# 08-DPLL-2.net
KiCad netlist of a schematic drawn in Altium Designer
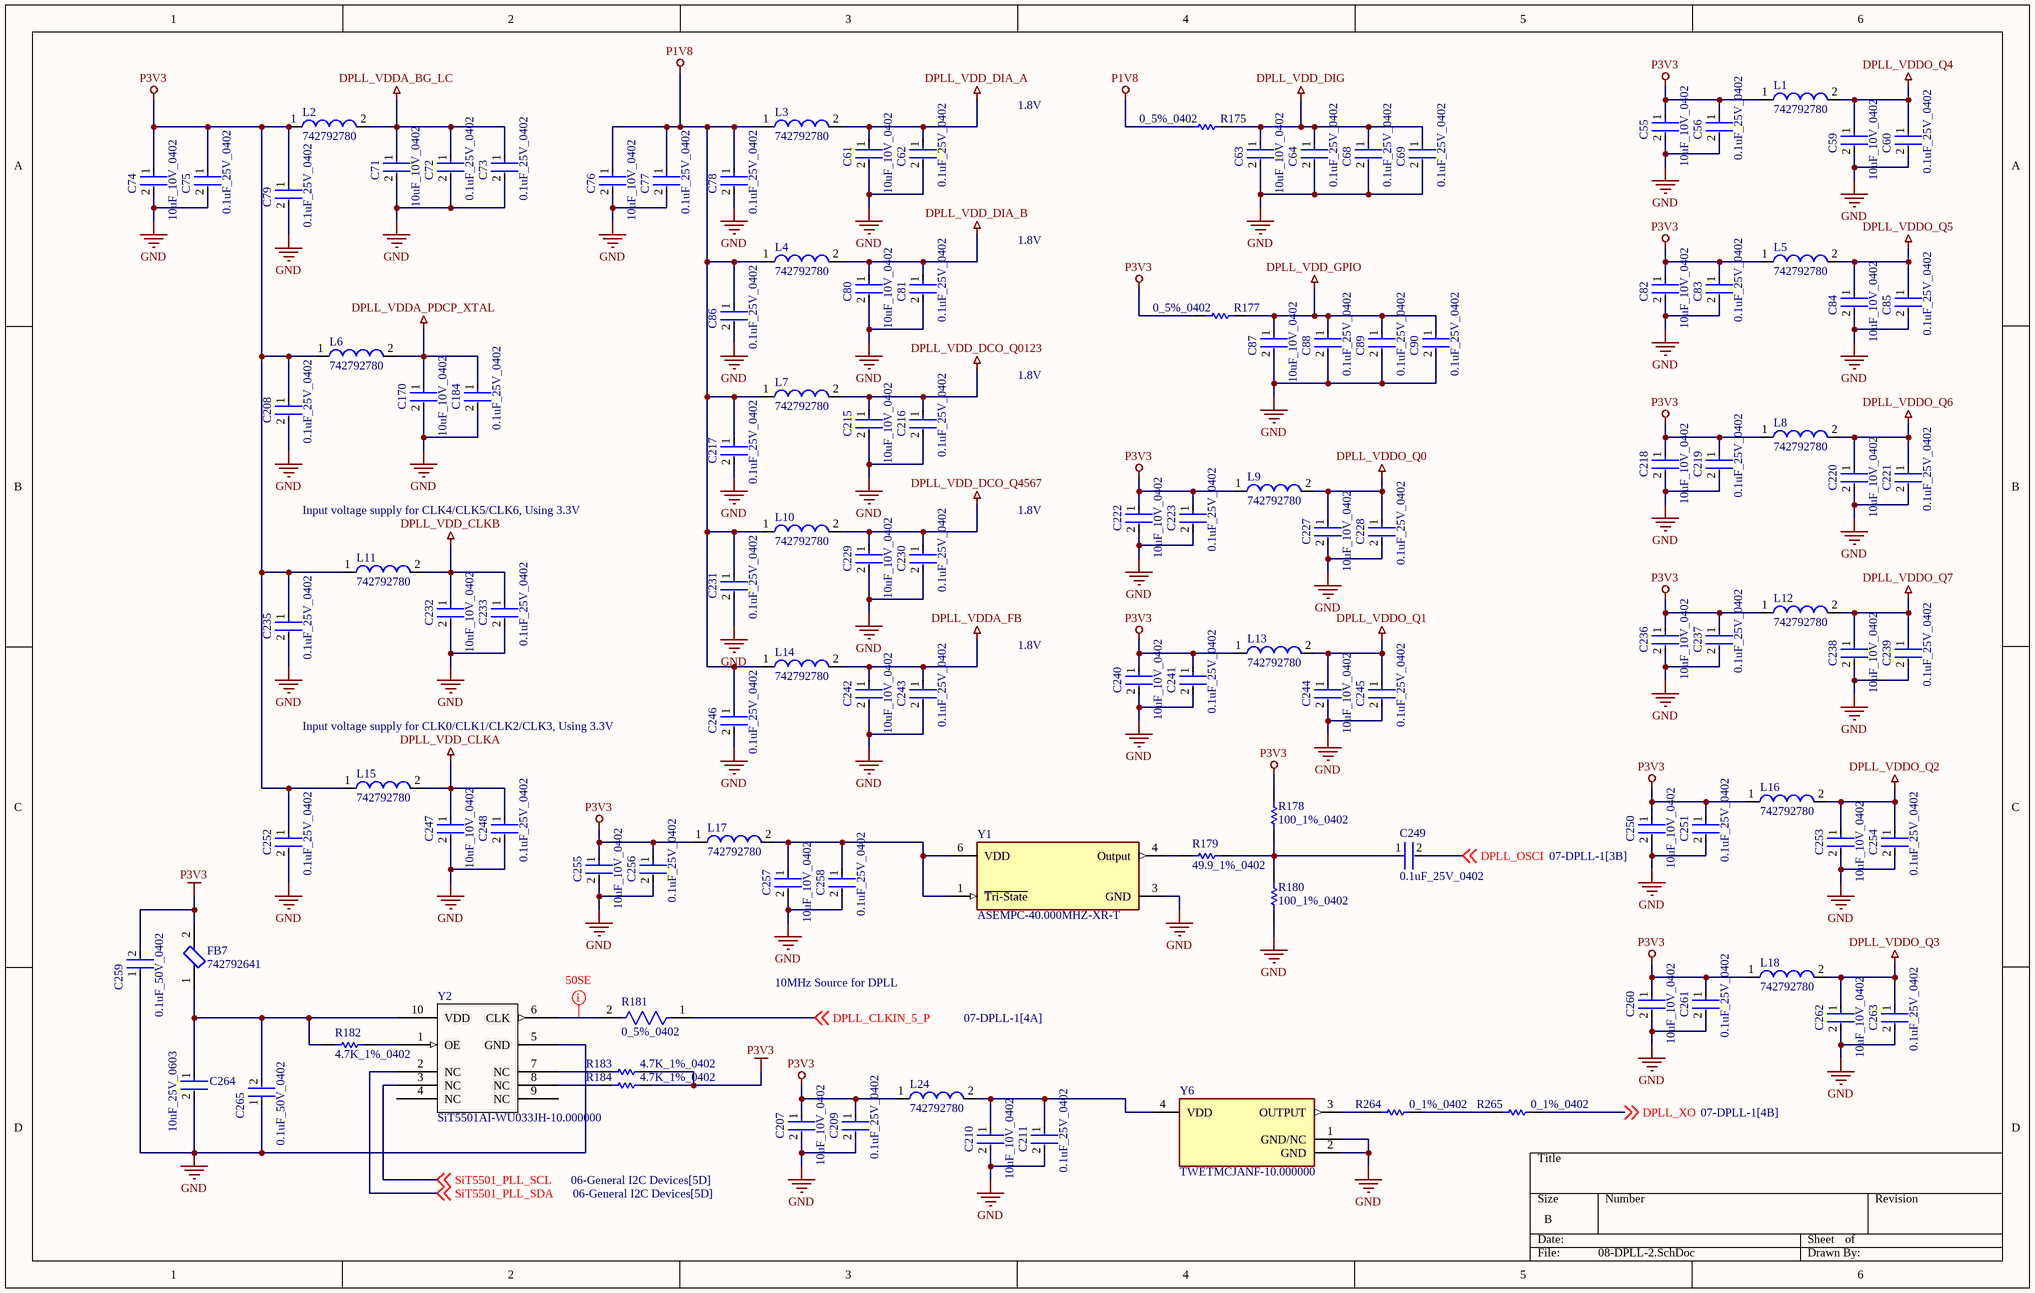
[diagram p0: 08-DPLL-2.SchDoc]

(export (version "E")
  (design (tool "Eeschema 10.0.6"))
  (components
    (comp (ref "C55")
      (value "10uF_10V_0402")
      (footprint "FP-CL05A106MP5NUNC-MFG")
      (description "CAP CER 10UF 10V X5R 0402")
      (fields
        (field (name "OCTOPART") "https://octopart.com/cl05a106mp5nunc-samsung-22457395")
        (field (name "TOLERANCE") "20%")
      )
      (libsource (lib "Altium Content Vault") (part "b4654b650e69147ec39a6b967a45e02"))
    )
    (comp (ref "C56")
      (value "0.1uF_25V_0402")
      (footprint "FP-0402-L_1_0_1-W_0_5_0_1-IPC_C")
      (description "General Purpose Ceramic Capacitor, 0402, 100nF, 10%, X7R, 15%, 25V")
      (fields (field (name "VOLTAGE") "25V") (field (name "TOLERANCE") "10%"))
      (libsource (lib "Altium Content Vault") (part "b4654b650e69147ec39a6b967a45e02"))
    )
    (comp (ref "C59")
      (value "10uF_10V_0402")
      (footprint "FP-CL05A106MP5NUNC-MFG")
      (description "CAP CER 10UF 10V X5R 0402")
      (fields
        (field (name "OCTOPART") "https://octopart.com/cl05a106mp5nunc-samsung-22457395")
        (field (name "TOLERANCE") "20%")
      )
      (libsource (lib "Altium Content Vault") (part "b4654b650e69147ec39a6b967a45e02"))
    )
    (comp (ref "C60")
      (value "0.1uF_25V_0402")
      (footprint "FP-0402-L_1_0_1-W_0_5_0_1-IPC_C")
      (description "General Purpose Ceramic Capacitor, 0402, 100nF, 10%, X7R, 15%, 25V")
      (fields (field (name "VOLTAGE") "25V") (field (name "TOLERANCE") "10%"))
      (libsource (lib "Altium Content Vault") (part "b4654b650e69147ec39a6b967a45e02"))
    )
    (comp (ref "C61")
      (value "10uF_10V_0402")
      (footprint "FP-CL05A106MP5NUNC-MFG")
      (description "CAP CER 10UF 10V X5R 0402")
      (fields
        (field (name "OCTOPART") "https://octopart.com/cl05a106mp5nunc-samsung-22457395")
        (field (name "TOLERANCE") "20%")
      )
      (libsource (lib "Altium Content Vault") (part "b4654b650e69147ec39a6b967a45e02"))
    )
    (comp (ref "C62")
      (value "0.1uF_25V_0402")
      (footprint "FP-0402-L_1_0_1-W_0_5_0_1-IPC_C")
      (description "General Purpose Ceramic Capacitor, 0402, 100nF, 10%, X7R, 15%, 25V")
      (fields (field (name "VOLTAGE") "25V") (field (name "TOLERANCE") "10%"))
      (libsource (lib "Altium Content Vault") (part "b4654b650e69147ec39a6b967a45e02"))
    )
    (comp (ref "C63")
      (value "10uF_10V_0402")
      (footprint "FP-CL05A106MP5NUNC-MFG")
      (description "CAP CER 10UF 10V X5R 0402")
      (fields
        (field (name "OCTOPART") "https://octopart.com/cl05a106mp5nunc-samsung-22457395")
        (field (name "TOLERANCE") "20%")
      )
      (libsource (lib "Altium Content Vault") (part "b4654b650e69147ec39a6b967a45e02"))
    )
    (comp (ref "C64")
      (value "0.1uF_25V_0402")
      (footprint "FP-0402-L_1_0_1-W_0_5_0_1-IPC_C")
      (description "General Purpose Ceramic Capacitor, 0402, 100nF, 10%, X7R, 15%, 25V")
      (fields (field (name "VOLTAGE") "25V") (field (name "TOLERANCE") "10%"))
      (libsource (lib "Altium Content Vault") (part "b4654b650e69147ec39a6b967a45e02"))
    )
    (comp (ref "C68")
      (value "0.1uF_25V_0402")
      (footprint "FP-0402-L_1_0_1-W_0_5_0_1-IPC_C")
      (description "General Purpose Ceramic Capacitor, 0402, 100nF, 10%, X7R, 15%, 25V")
      (fields (field (name "VOLTAGE") "25V") (field (name "TOLERANCE") "10%"))
      (libsource (lib "Altium Content Vault") (part "b4654b650e69147ec39a6b967a45e02"))
    )
    (comp (ref "C69")
      (value "0.1uF_25V_0402")
      (footprint "FP-0402-L_1_0_1-W_0_5_0_1-IPC_C")
      (description "General Purpose Ceramic Capacitor, 0402, 100nF, 10%, X7R, 15%, 25V")
      (fields (field (name "VOLTAGE") "25V") (field (name "TOLERANCE") "10%"))
      (libsource (lib "Altium Content Vault") (part "b4654b650e69147ec39a6b967a45e02"))
    )
    (comp (ref "C71")
      (value "10uF_10V_0402")
      (footprint "FP-CL05A106MP5NUNC-MFG")
      (description "CAP CER 10UF 10V X5R 0402")
      (fields
        (field (name "OCTOPART") "https://octopart.com/cl05a106mp5nunc-samsung-22457395")
        (field (name "TOLERANCE") "20%")
      )
      (libsource (lib "Altium Content Vault") (part "b4654b650e69147ec39a6b967a45e02"))
    )
    (comp (ref "C72")
      (value "0.1uF_25V_0402")
      (footprint "FP-0402-L_1_0_1-W_0_5_0_1-IPC_C")
      (description "General Purpose Ceramic Capacitor, 0402, 100nF, 10%, X7R, 15%, 25V")
      (fields (field (name "VOLTAGE") "25V") (field (name "TOLERANCE") "10%"))
      (libsource (lib "Altium Content Vault") (part "b4654b650e69147ec39a6b967a45e02"))
    )
    (comp (ref "C73")
      (value "0.1uF_25V_0402")
      (footprint "FP-0402-L_1_0_1-W_0_5_0_1-IPC_C")
      (description "General Purpose Ceramic Capacitor, 0402, 100nF, 10%, X7R, 15%, 25V")
      (fields (field (name "VOLTAGE") "25V") (field (name "TOLERANCE") "10%"))
      (libsource (lib "Altium Content Vault") (part "b4654b650e69147ec39a6b967a45e02"))
    )
    (comp (ref "C74")
      (value "10uF_10V_0402")
      (footprint "FP-CL05A106MP5NUNC-MFG")
      (description "CAP CER 10UF 10V X5R 0402")
      (fields
        (field (name "OCTOPART") "https://octopart.com/cl05a106mp5nunc-samsung-22457395")
        (field (name "TOLERANCE") "20%")
      )
      (libsource (lib "Altium Content Vault") (part "b4654b650e69147ec39a6b967a45e02"))
    )
    (comp (ref "C75")
      (value "0.1uF_25V_0402")
      (footprint "FP-0402-L_1_0_1-W_0_5_0_1-IPC_C")
      (description "General Purpose Ceramic Capacitor, 0402, 100nF, 10%, X7R, 15%, 25V")
      (fields (field (name "VOLTAGE") "25V") (field (name "TOLERANCE") "10%"))
      (libsource (lib "Altium Content Vault") (part "b4654b650e69147ec39a6b967a45e02"))
    )
    (comp (ref "C76")
      (value "10uF_10V_0402")
      (footprint "FP-CL05A106MP5NUNC-MFG")
      (description "CAP CER 10UF 10V X5R 0402")
      (fields
        (field (name "OCTOPART") "https://octopart.com/cl05a106mp5nunc-samsung-22457395")
        (field (name "TOLERANCE") "20%")
      )
      (libsource (lib "Altium Content Vault") (part "b4654b650e69147ec39a6b967a45e02"))
    )
    (comp (ref "C77")
      (value "0.1uF_25V_0402")
      (footprint "FP-0402-L_1_0_1-W_0_5_0_1-IPC_C")
      (description "General Purpose Ceramic Capacitor, 0402, 100nF, 10%, X7R, 15%, 25V")
      (fields (field (name "VOLTAGE") "25V") (field (name "TOLERANCE") "10%"))
      (libsource (lib "Altium Content Vault") (part "b4654b650e69147ec39a6b967a45e02"))
    )
    (comp (ref "C78")
      (value "0.1uF_25V_0402")
      (footprint "FP-0402-L_1_0_1-W_0_5_0_1-IPC_C")
      (description "General Purpose Ceramic Capacitor, 0402, 100nF, 10%, X7R, 15%, 25V")
      (fields (field (name "VOLTAGE") "25V") (field (name "TOLERANCE") "10%"))
      (libsource (lib "Altium Content Vault") (part "b4654b650e69147ec39a6b967a45e02"))
    )
    (comp (ref "C79")
      (value "0.1uF_25V_0402")
      (footprint "FP-0402-L_1_0_1-W_0_5_0_1-IPC_C")
      (description "General Purpose Ceramic Capacitor, 0402, 100nF, 10%, X7R, 15%, 25V")
      (fields (field (name "VOLTAGE") "25V") (field (name "TOLERANCE") "10%"))
      (libsource (lib "Altium Content Vault") (part "b4654b650e69147ec39a6b967a45e02"))
    )
    (comp (ref "C80")
      (value "10uF_10V_0402")
      (footprint "FP-CL05A106MP5NUNC-MFG")
      (description "CAP CER 10UF 10V X5R 0402")
      (fields
        (field (name "OCTOPART") "https://octopart.com/cl05a106mp5nunc-samsung-22457395")
        (field (name "TOLERANCE") "20%")
      )
      (libsource (lib "Altium Content Vault") (part "b4654b650e69147ec39a6b967a45e02"))
    )
    (comp (ref "C81")
      (value "0.1uF_25V_0402")
      (footprint "FP-0402-L_1_0_1-W_0_5_0_1-IPC_C")
      (description "General Purpose Ceramic Capacitor, 0402, 100nF, 10%, X7R, 15%, 25V")
      (fields (field (name "VOLTAGE") "25V") (field (name "TOLERANCE") "10%"))
      (libsource (lib "Altium Content Vault") (part "b4654b650e69147ec39a6b967a45e02"))
    )
    (comp (ref "C82")
      (value "10uF_10V_0402")
      (footprint "FP-CL05A106MP5NUNC-MFG")
      (description "CAP CER 10UF 10V X5R 0402")
      (fields
        (field (name "OCTOPART") "https://octopart.com/cl05a106mp5nunc-samsung-22457395")
        (field (name "TOLERANCE") "20%")
      )
      (libsource (lib "Altium Content Vault") (part "b4654b650e69147ec39a6b967a45e02"))
    )
    (comp (ref "C83")
      (value "0.1uF_25V_0402")
      (footprint "FP-0402-L_1_0_1-W_0_5_0_1-IPC_C")
      (description "General Purpose Ceramic Capacitor, 0402, 100nF, 10%, X7R, 15%, 25V")
      (fields (field (name "VOLTAGE") "25V") (field (name "TOLERANCE") "10%"))
      (libsource (lib "Altium Content Vault") (part "b4654b650e69147ec39a6b967a45e02"))
    )
    (comp (ref "C84")
      (value "10uF_10V_0402")
      (footprint "FP-CL05A106MP5NUNC-MFG")
      (description "CAP CER 10UF 10V X5R 0402")
      (fields
        (field (name "OCTOPART") "https://octopart.com/cl05a106mp5nunc-samsung-22457395")
        (field (name "TOLERANCE") "20%")
      )
      (libsource (lib "Altium Content Vault") (part "b4654b650e69147ec39a6b967a45e02"))
    )
    (comp (ref "C85")
      (value "0.1uF_25V_0402")
      (footprint "FP-0402-L_1_0_1-W_0_5_0_1-IPC_C")
      (description "General Purpose Ceramic Capacitor, 0402, 100nF, 10%, X7R, 15%, 25V")
      (fields (field (name "VOLTAGE") "25V") (field (name "TOLERANCE") "10%"))
      (libsource (lib "Altium Content Vault") (part "b4654b650e69147ec39a6b967a45e02"))
    )
    (comp (ref "C86")
      (value "0.1uF_25V_0402")
      (footprint "FP-0402-L_1_0_1-W_0_5_0_1-IPC_C")
      (description "General Purpose Ceramic Capacitor, 0402, 100nF, 10%, X7R, 15%, 25V")
      (fields (field (name "VOLTAGE") "25V") (field (name "TOLERANCE") "10%"))
      (libsource (lib "Altium Content Vault") (part "b4654b650e69147ec39a6b967a45e02"))
    )
    (comp (ref "C87")
      (value "10uF_10V_0402")
      (footprint "FP-CL05A106MP5NUNC-MFG")
      (description "CAP CER 10UF 10V X5R 0402")
      (fields
        (field (name "OCTOPART") "https://octopart.com/cl05a106mp5nunc-samsung-22457395")
        (field (name "TOLERANCE") "20%")
      )
      (libsource (lib "Altium Content Vault") (part "b4654b650e69147ec39a6b967a45e02"))
    )
    (comp (ref "C88")
      (value "0.1uF_25V_0402")
      (footprint "FP-0402-L_1_0_1-W_0_5_0_1-IPC_C")
      (description "General Purpose Ceramic Capacitor, 0402, 100nF, 10%, X7R, 15%, 25V")
      (fields (field (name "VOLTAGE") "25V") (field (name "TOLERANCE") "10%"))
      (libsource (lib "Altium Content Vault") (part "b4654b650e69147ec39a6b967a45e02"))
    )
    (comp (ref "C89")
      (value "0.1uF_25V_0402")
      (footprint "FP-0402-L_1_0_1-W_0_5_0_1-IPC_C")
      (description "General Purpose Ceramic Capacitor, 0402, 100nF, 10%, X7R, 15%, 25V")
      (fields (field (name "VOLTAGE") "25V") (field (name "TOLERANCE") "10%"))
      (libsource (lib "Altium Content Vault") (part "b4654b650e69147ec39a6b967a45e02"))
    )
    (comp (ref "C90")
      (value "0.1uF_25V_0402")
      (footprint "FP-0402-L_1_0_1-W_0_5_0_1-IPC_C")
      (description "General Purpose Ceramic Capacitor, 0402, 100nF, 10%, X7R, 15%, 25V")
      (fields (field (name "VOLTAGE") "25V") (field (name "TOLERANCE") "10%"))
      (libsource (lib "Altium Content Vault") (part "b4654b650e69147ec39a6b967a45e02"))
    )
    (comp (ref "C170")
      (value "10uF_10V_0402")
      (footprint "FP-CL05A106MP5NUNC-MFG")
      (description "CAP CER 10UF 10V X5R 0402")
      (fields
        (field (name "OCTOPART") "https://octopart.com/cl05a106mp5nunc-samsung-22457395")
        (field (name "TOLERANCE") "20%")
      )
      (libsource (lib "Altium Content Vault") (part "b4654b650e69147ec39a6b967a45e02"))
    )
    (comp (ref "C184")
      (value "0.1uF_25V_0402")
      (footprint "FP-0402-L_1_0_1-W_0_5_0_1-IPC_C")
      (description "General Purpose Ceramic Capacitor, 0402, 100nF, 10%, X7R, 15%, 25V")
      (fields (field (name "VOLTAGE") "25V") (field (name "TOLERANCE") "10%"))
      (libsource (lib "Altium Content Vault") (part "b4654b650e69147ec39a6b967a45e02"))
    )
    (comp (ref "C207")
      (value "10uF_10V_0402")
      (footprint "FP-CL05A106MP5NUNC-MFG")
      (description "CAP CER 10UF 10V X5R 0402")
      (fields
        (field (name "OCTOPART") "https://octopart.com/cl05a106mp5nunc-samsung-22457395")
        (field (name "TOLERANCE") "20%")
      )
      (libsource (lib "Altium Content Vault") (part "b4654b650e69147ec39a6b967a45e02"))
    )
    (comp (ref "C208")
      (value "0.1uF_25V_0402")
      (footprint "FP-0402-L_1_0_1-W_0_5_0_1-IPC_C")
      (description "General Purpose Ceramic Capacitor, 0402, 100nF, 10%, X7R, 15%, 25V")
      (fields (field (name "VOLTAGE") "25V") (field (name "TOLERANCE") "10%"))
      (libsource (lib "Altium Content Vault") (part "b4654b650e69147ec39a6b967a45e02"))
    )
    (comp (ref "C209")
      (value "0.1uF_25V_0402")
      (footprint "FP-0402-L_1_0_1-W_0_5_0_1-IPC_C")
      (description "General Purpose Ceramic Capacitor, 0402, 100nF, 10%, X7R, 15%, 25V")
      (fields (field (name "VOLTAGE") "25V") (field (name "TOLERANCE") "10%"))
      (libsource (lib "Altium Content Vault") (part "b4654b650e69147ec39a6b967a45e02"))
    )
    (comp (ref "C210")
      (value "10uF_10V_0402")
      (footprint "FP-CL05A106MP5NUNC-MFG")
      (description "CAP CER 10UF 10V X5R 0402")
      (fields
        (field (name "OCTOPART") "https://octopart.com/cl05a106mp5nunc-samsung-22457395")
        (field (name "TOLERANCE") "20%")
      )
      (libsource (lib "Altium Content Vault") (part "b4654b650e69147ec39a6b967a45e02"))
    )
    (comp (ref "C211")
      (value "0.1uF_25V_0402")
      (footprint "FP-0402-L_1_0_1-W_0_5_0_1-IPC_C")
      (description "General Purpose Ceramic Capacitor, 0402, 100nF, 10%, X7R, 15%, 25V")
      (fields (field (name "VOLTAGE") "25V") (field (name "TOLERANCE") "10%"))
      (libsource (lib "Altium Content Vault") (part "b4654b650e69147ec39a6b967a45e02"))
    )
    (comp (ref "C215")
      (value "10uF_10V_0402")
      (footprint "FP-CL05A106MP5NUNC-MFG")
      (description "CAP CER 10UF 10V X5R 0402")
      (fields
        (field (name "OCTOPART") "https://octopart.com/cl05a106mp5nunc-samsung-22457395")
        (field (name "TOLERANCE") "20%")
      )
      (libsource (lib "Altium Content Vault") (part "b4654b650e69147ec39a6b967a45e02"))
    )
    (comp (ref "C216")
      (value "0.1uF_25V_0402")
      (footprint "FP-0402-L_1_0_1-W_0_5_0_1-IPC_C")
      (description "General Purpose Ceramic Capacitor, 0402, 100nF, 10%, X7R, 15%, 25V")
      (fields (field (name "VOLTAGE") "25V") (field (name "TOLERANCE") "10%"))
      (libsource (lib "Altium Content Vault") (part "b4654b650e69147ec39a6b967a45e02"))
    )
    (comp (ref "C217")
      (value "0.1uF_25V_0402")
      (footprint "FP-0402-L_1_0_1-W_0_5_0_1-IPC_C")
      (description "General Purpose Ceramic Capacitor, 0402, 100nF, 10%, X7R, 15%, 25V")
      (fields (field (name "VOLTAGE") "25V") (field (name "TOLERANCE") "10%"))
      (libsource (lib "Altium Content Vault") (part "b4654b650e69147ec39a6b967a45e02"))
    )
    (comp (ref "C218")
      (value "10uF_10V_0402")
      (footprint "FP-CL05A106MP5NUNC-MFG")
      (description "CAP CER 10UF 10V X5R 0402")
      (fields
        (field (name "OCTOPART") "https://octopart.com/cl05a106mp5nunc-samsung-22457395")
        (field (name "TOLERANCE") "20%")
      )
      (libsource (lib "Altium Content Vault") (part "b4654b650e69147ec39a6b967a45e02"))
    )
    (comp (ref "C219")
      (value "0.1uF_25V_0402")
      (footprint "FP-0402-L_1_0_1-W_0_5_0_1-IPC_C")
      (description "General Purpose Ceramic Capacitor, 0402, 100nF, 10%, X7R, 15%, 25V")
      (fields (field (name "VOLTAGE") "25V") (field (name "TOLERANCE") "10%"))
      (libsource (lib "Altium Content Vault") (part "b4654b650e69147ec39a6b967a45e02"))
    )
    (comp (ref "C220")
      (value "10uF_10V_0402")
      (footprint "FP-CL05A106MP5NUNC-MFG")
      (description "CAP CER 10UF 10V X5R 0402")
      (fields
        (field (name "OCTOPART") "https://octopart.com/cl05a106mp5nunc-samsung-22457395")
        (field (name "TOLERANCE") "20%")
      )
      (libsource (lib "Altium Content Vault") (part "b4654b650e69147ec39a6b967a45e02"))
    )
    (comp (ref "C221")
      (value "0.1uF_25V_0402")
      (footprint "FP-0402-L_1_0_1-W_0_5_0_1-IPC_C")
      (description "General Purpose Ceramic Capacitor, 0402, 100nF, 10%, X7R, 15%, 25V")
      (fields (field (name "VOLTAGE") "25V") (field (name "TOLERANCE") "10%"))
      (libsource (lib "Altium Content Vault") (part "b4654b650e69147ec39a6b967a45e02"))
    )
    (comp (ref "C222")
      (value "10uF_10V_0402")
      (footprint "FP-CL05A106MP5NUNC-MFG")
      (description "CAP CER 10UF 10V X5R 0402")
      (fields
        (field (name "OCTOPART") "https://octopart.com/cl05a106mp5nunc-samsung-22457395")
        (field (name "TOLERANCE") "20%")
      )
      (libsource (lib "Altium Content Vault") (part "b4654b650e69147ec39a6b967a45e02"))
    )
    (comp (ref "C223")
      (value "0.1uF_25V_0402")
      (footprint "FP-0402-L_1_0_1-W_0_5_0_1-IPC_C")
      (description "General Purpose Ceramic Capacitor, 0402, 100nF, 10%, X7R, 15%, 25V")
      (fields (field (name "VOLTAGE") "25V") (field (name "TOLERANCE") "10%"))
      (libsource (lib "Altium Content Vault") (part "b4654b650e69147ec39a6b967a45e02"))
    )
    (comp (ref "C227")
      (value "10uF_10V_0402")
      (footprint "FP-CL05A106MP5NUNC-MFG")
      (description "CAP CER 10UF 10V X5R 0402")
      (fields
        (field (name "OCTOPART") "https://octopart.com/cl05a106mp5nunc-samsung-22457395")
        (field (name "TOLERANCE") "20%")
      )
      (libsource (lib "Altium Content Vault") (part "b4654b650e69147ec39a6b967a45e02"))
    )
    (comp (ref "C228")
      (value "0.1uF_25V_0402")
      (footprint "FP-0402-L_1_0_1-W_0_5_0_1-IPC_C")
      (description "General Purpose Ceramic Capacitor, 0402, 100nF, 10%, X7R, 15%, 25V")
      (fields (field (name "VOLTAGE") "25V") (field (name "TOLERANCE") "10%"))
      (libsource (lib "Altium Content Vault") (part "b4654b650e69147ec39a6b967a45e02"))
    )
    (comp (ref "C229")
      (value "10uF_10V_0402")
      (footprint "FP-CL05A106MP5NUNC-MFG")
      (description "CAP CER 10UF 10V X5R 0402")
      (fields
        (field (name "OCTOPART") "https://octopart.com/cl05a106mp5nunc-samsung-22457395")
        (field (name "TOLERANCE") "20%")
      )
      (libsource (lib "Altium Content Vault") (part "b4654b650e69147ec39a6b967a45e02"))
    )
    (comp (ref "C230")
      (value "0.1uF_25V_0402")
      (footprint "FP-0402-L_1_0_1-W_0_5_0_1-IPC_C")
      (description "General Purpose Ceramic Capacitor, 0402, 100nF, 10%, X7R, 15%, 25V")
      (fields (field (name "VOLTAGE") "25V") (field (name "TOLERANCE") "10%"))
      (libsource (lib "Altium Content Vault") (part "b4654b650e69147ec39a6b967a45e02"))
    )
    (comp (ref "C231")
      (value "0.1uF_25V_0402")
      (footprint "FP-0402-L_1_0_1-W_0_5_0_1-IPC_C")
      (description "General Purpose Ceramic Capacitor, 0402, 100nF, 10%, X7R, 15%, 25V")
      (fields (field (name "VOLTAGE") "25V") (field (name "TOLERANCE") "10%"))
      (libsource (lib "Altium Content Vault") (part "b4654b650e69147ec39a6b967a45e02"))
    )
    (comp (ref "C232")
      (value "10uF_10V_0402")
      (footprint "FP-CL05A106MP5NUNC-MFG")
      (description "CAP CER 10UF 10V X5R 0402")
      (fields
        (field (name "OCTOPART") "https://octopart.com/cl05a106mp5nunc-samsung-22457395")
        (field (name "TOLERANCE") "20%")
      )
      (libsource (lib "Altium Content Vault") (part "b4654b650e69147ec39a6b967a45e02"))
    )
    (comp (ref "C233")
      (value "0.1uF_25V_0402")
      (footprint "FP-0402-L_1_0_1-W_0_5_0_1-IPC_C")
      (description "General Purpose Ceramic Capacitor, 0402, 100nF, 10%, X7R, 15%, 25V")
      (fields (field (name "VOLTAGE") "25V") (field (name "TOLERANCE") "10%"))
      (libsource (lib "Altium Content Vault") (part "b4654b650e69147ec39a6b967a45e02"))
    )
    (comp (ref "C235")
      (value "0.1uF_25V_0402")
      (footprint "FP-0402-L_1_0_1-W_0_5_0_1-IPC_C")
      (description "General Purpose Ceramic Capacitor, 0402, 100nF, 10%, X7R, 15%, 25V")
      (fields (field (name "VOLTAGE") "25V") (field (name "TOLERANCE") "10%"))
      (libsource (lib "Altium Content Vault") (part "b4654b650e69147ec39a6b967a45e02"))
    )
    (comp (ref "C236")
      (value "10uF_10V_0402")
      (footprint "FP-CL05A106MP5NUNC-MFG")
      (description "CAP CER 10UF 10V X5R 0402")
      (fields
        (field (name "OCTOPART") "https://octopart.com/cl05a106mp5nunc-samsung-22457395")
        (field (name "TOLERANCE") "20%")
      )
      (libsource (lib "Altium Content Vault") (part "b4654b650e69147ec39a6b967a45e02"))
    )
    (comp (ref "C237")
      (value "0.1uF_25V_0402")
      (footprint "FP-0402-L_1_0_1-W_0_5_0_1-IPC_C")
      (description "General Purpose Ceramic Capacitor, 0402, 100nF, 10%, X7R, 15%, 25V")
      (fields (field (name "VOLTAGE") "25V") (field (name "TOLERANCE") "10%"))
      (libsource (lib "Altium Content Vault") (part "b4654b650e69147ec39a6b967a45e02"))
    )
    (comp (ref "C238")
      (value "10uF_10V_0402")
      (footprint "FP-CL05A106MP5NUNC-MFG")
      (description "CAP CER 10UF 10V X5R 0402")
      (fields
        (field (name "OCTOPART") "https://octopart.com/cl05a106mp5nunc-samsung-22457395")
        (field (name "TOLERANCE") "20%")
      )
      (libsource (lib "Altium Content Vault") (part "b4654b650e69147ec39a6b967a45e02"))
    )
    (comp (ref "C239")
      (value "0.1uF_25V_0402")
      (footprint "FP-0402-L_1_0_1-W_0_5_0_1-IPC_C")
      (description "General Purpose Ceramic Capacitor, 0402, 100nF, 10%, X7R, 15%, 25V")
      (fields (field (name "VOLTAGE") "25V") (field (name "TOLERANCE") "10%"))
      (libsource (lib "Altium Content Vault") (part "b4654b650e69147ec39a6b967a45e02"))
    )
    (comp (ref "C240")
      (value "10uF_10V_0402")
      (footprint "FP-CL05A106MP5NUNC-MFG")
      (description "CAP CER 10UF 10V X5R 0402")
      (fields
        (field (name "OCTOPART") "https://octopart.com/cl05a106mp5nunc-samsung-22457395")
        (field (name "TOLERANCE") "20%")
      )
      (libsource (lib "Altium Content Vault") (part "b4654b650e69147ec39a6b967a45e02"))
    )
    (comp (ref "C241")
      (value "0.1uF_25V_0402")
      (footprint "FP-0402-L_1_0_1-W_0_5_0_1-IPC_C")
      (description "General Purpose Ceramic Capacitor, 0402, 100nF, 10%, X7R, 15%, 25V")
      (fields (field (name "VOLTAGE") "25V") (field (name "TOLERANCE") "10%"))
      (libsource (lib "Altium Content Vault") (part "b4654b650e69147ec39a6b967a45e02"))
    )
    (comp (ref "C242")
      (value "10uF_10V_0402")
      (footprint "FP-CL05A106MP5NUNC-MFG")
      (description "CAP CER 10UF 10V X5R 0402")
      (fields
        (field (name "OCTOPART") "https://octopart.com/cl05a106mp5nunc-samsung-22457395")
        (field (name "TOLERANCE") "20%")
      )
      (libsource (lib "Altium Content Vault") (part "b4654b650e69147ec39a6b967a45e02"))
    )
    (comp (ref "C243")
      (value "0.1uF_25V_0402")
      (footprint "FP-0402-L_1_0_1-W_0_5_0_1-IPC_C")
      (description "General Purpose Ceramic Capacitor, 0402, 100nF, 10%, X7R, 15%, 25V")
      (fields (field (name "VOLTAGE") "25V") (field (name "TOLERANCE") "10%"))
      (libsource (lib "Altium Content Vault") (part "b4654b650e69147ec39a6b967a45e02"))
    )
    (comp (ref "C244")
      (value "10uF_10V_0402")
      (footprint "FP-CL05A106MP5NUNC-MFG")
      (description "CAP CER 10UF 10V X5R 0402")
      (fields
        (field (name "OCTOPART") "https://octopart.com/cl05a106mp5nunc-samsung-22457395")
        (field (name "TOLERANCE") "20%")
      )
      (libsource (lib "Altium Content Vault") (part "b4654b650e69147ec39a6b967a45e02"))
    )
    (comp (ref "C245")
      (value "0.1uF_25V_0402")
      (footprint "FP-0402-L_1_0_1-W_0_5_0_1-IPC_C")
      (description "General Purpose Ceramic Capacitor, 0402, 100nF, 10%, X7R, 15%, 25V")
      (fields (field (name "VOLTAGE") "25V") (field (name "TOLERANCE") "10%"))
      (libsource (lib "Altium Content Vault") (part "b4654b650e69147ec39a6b967a45e02"))
    )
    (comp (ref "C246")
      (value "0.1uF_25V_0402")
      (footprint "FP-0402-L_1_0_1-W_0_5_0_1-IPC_C")
      (description "General Purpose Ceramic Capacitor, 0402, 100nF, 10%, X7R, 15%, 25V")
      (fields (field (name "VOLTAGE") "25V") (field (name "TOLERANCE") "10%"))
      (libsource (lib "Altium Content Vault") (part "b4654b650e69147ec39a6b967a45e02"))
    )
    (comp (ref "C247")
      (value "10uF_10V_0402")
      (footprint "FP-CL05A106MP5NUNC-MFG")
      (description "CAP CER 10UF 10V X5R 0402")
      (fields
        (field (name "OCTOPART") "https://octopart.com/cl05a106mp5nunc-samsung-22457395")
        (field (name "TOLERANCE") "20%")
      )
      (libsource (lib "Altium Content Vault") (part "b4654b650e69147ec39a6b967a45e02"))
    )
    (comp (ref "C248")
      (value "0.1uF_25V_0402")
      (footprint "FP-0402-L_1_0_1-W_0_5_0_1-IPC_C")
      (description "General Purpose Ceramic Capacitor, 0402, 100nF, 10%, X7R, 15%, 25V")
      (fields (field (name "VOLTAGE") "25V") (field (name "TOLERANCE") "10%"))
      (libsource (lib "Altium Content Vault") (part "b4654b650e69147ec39a6b967a45e02"))
    )
    (comp (ref "C249")
      (value "0.1uF_25V_0402")
      (footprint "FP-0402-L_1_0_1-W_0_5_0_1-IPC_C")
      (description "General Purpose Ceramic Capacitor, 0402, 100nF, 10%, X7R, 15%, 25V")
      (fields (field (name "VOLTAGE") "25V") (field (name "TOLERANCE") "10%"))
      (libsource (lib "Altium Content Vault") (part "b4654b650e69147ec39a6b967a45e02"))
    )
    (comp (ref "C250")
      (value "10uF_10V_0402")
      (footprint "FP-CL05A106MP5NUNC-MFG")
      (description "CAP CER 10UF 10V X5R 0402")
      (fields
        (field (name "OCTOPART") "https://octopart.com/cl05a106mp5nunc-samsung-22457395")
        (field (name "TOLERANCE") "20%")
      )
      (libsource (lib "Altium Content Vault") (part "b4654b650e69147ec39a6b967a45e02"))
    )
    (comp (ref "C251")
      (value "0.1uF_25V_0402")
      (footprint "FP-0402-L_1_0_1-W_0_5_0_1-IPC_C")
      (description "General Purpose Ceramic Capacitor, 0402, 100nF, 10%, X7R, 15%, 25V")
      (fields (field (name "VOLTAGE") "25V") (field (name "TOLERANCE") "10%"))
      (libsource (lib "Altium Content Vault") (part "b4654b650e69147ec39a6b967a45e02"))
    )
    (comp (ref "C252")
      (value "0.1uF_25V_0402")
      (footprint "FP-0402-L_1_0_1-W_0_5_0_1-IPC_C")
      (description "General Purpose Ceramic Capacitor, 0402, 100nF, 10%, X7R, 15%, 25V")
      (fields (field (name "VOLTAGE") "25V") (field (name "TOLERANCE") "10%"))
      (libsource (lib "Altium Content Vault") (part "b4654b650e69147ec39a6b967a45e02"))
    )
    (comp (ref "C253")
      (value "10uF_10V_0402")
      (footprint "FP-CL05A106MP5NUNC-MFG")
      (description "CAP CER 10UF 10V X5R 0402")
      (fields
        (field (name "OCTOPART") "https://octopart.com/cl05a106mp5nunc-samsung-22457395")
        (field (name "TOLERANCE") "20%")
      )
      (libsource (lib "Altium Content Vault") (part "b4654b650e69147ec39a6b967a45e02"))
    )
    (comp (ref "C254")
      (value "0.1uF_25V_0402")
      (footprint "FP-0402-L_1_0_1-W_0_5_0_1-IPC_C")
      (description "General Purpose Ceramic Capacitor, 0402, 100nF, 10%, X7R, 15%, 25V")
      (fields (field (name "VOLTAGE") "25V") (field (name "TOLERANCE") "10%"))
      (libsource (lib "Altium Content Vault") (part "b4654b650e69147ec39a6b967a45e02"))
    )
    (comp (ref "C255")
      (value "10uF_10V_0402")
      (footprint "FP-CL05A106MP5NUNC-MFG")
      (description "CAP CER 10UF 10V X5R 0402")
      (fields
        (field (name "OCTOPART") "https://octopart.com/cl05a106mp5nunc-samsung-22457395")
        (field (name "TOLERANCE") "20%")
      )
      (libsource (lib "Altium Content Vault") (part "b4654b650e69147ec39a6b967a45e02"))
    )
    (comp (ref "C256")
      (value "0.1uF_25V_0402")
      (footprint "FP-0402-L_1_0_1-W_0_5_0_1-IPC_C")
      (description "General Purpose Ceramic Capacitor, 0402, 100nF, 10%, X7R, 15%, 25V")
      (fields (field (name "VOLTAGE") "25V") (field (name "TOLERANCE") "10%"))
      (libsource (lib "Altium Content Vault") (part "b4654b650e69147ec39a6b967a45e02"))
    )
    (comp (ref "C257")
      (value "10uF_10V_0402")
      (footprint "FP-CL05A106MP5NUNC-MFG")
      (description "CAP CER 10UF 10V X5R 0402")
      (fields
        (field (name "OCTOPART") "https://octopart.com/cl05a106mp5nunc-samsung-22457395")
        (field (name "TOLERANCE") "20%")
      )
      (libsource (lib "Altium Content Vault") (part "b4654b650e69147ec39a6b967a45e02"))
    )
    (comp (ref "C258")
      (value "0.1uF_25V_0402")
      (footprint "FP-0402-L_1_0_1-W_0_5_0_1-IPC_C")
      (description "General Purpose Ceramic Capacitor, 0402, 100nF, 10%, X7R, 15%, 25V")
      (fields (field (name "VOLTAGE") "25V") (field (name "TOLERANCE") "10%"))
      (libsource (lib "Altium Content Vault") (part "b4654b650e69147ec39a6b967a45e02"))
    )
    (comp (ref "C259")
      (value "0.1uF_50V_0402")
      (footprint "FP-C1005-050-0_05-IPC_C")
      (description "Multilayer Ceramic Capacitors 100nF ±10% 50V X7R SMD 0402")
      (fields (field (name "VOLTAGE") "50V") (field (name "TOLERANCE") "10%"))
      (libsource (lib "Altium Content Vault") (part "b4654b650e69147ec39a6b967a45e02"))
    )
    (comp (ref "C260")
      (value "10uF_10V_0402")
      (footprint "FP-CL05A106MP5NUNC-MFG")
      (description "CAP CER 10UF 10V X5R 0402")
      (fields
        (field (name "OCTOPART") "https://octopart.com/cl05a106mp5nunc-samsung-22457395")
        (field (name "TOLERANCE") "20%")
      )
      (libsource (lib "Altium Content Vault") (part "b4654b650e69147ec39a6b967a45e02"))
    )
    (comp (ref "C261")
      (value "0.1uF_25V_0402")
      (footprint "FP-0402-L_1_0_1-W_0_5_0_1-IPC_C")
      (description "General Purpose Ceramic Capacitor, 0402, 100nF, 10%, X7R, 15%, 25V")
      (fields (field (name "VOLTAGE") "25V") (field (name "TOLERANCE") "10%"))
      (libsource (lib "Altium Content Vault") (part "b4654b650e69147ec39a6b967a45e02"))
    )
    (comp (ref "C262")
      (value "10uF_10V_0402")
      (footprint "FP-CL05A106MP5NUNC-MFG")
      (description "CAP CER 10UF 10V X5R 0402")
      (fields
        (field (name "OCTOPART") "https://octopart.com/cl05a106mp5nunc-samsung-22457395")
        (field (name "TOLERANCE") "20%")
      )
      (libsource (lib "Altium Content Vault") (part "b4654b650e69147ec39a6b967a45e02"))
    )
    (comp (ref "C263")
      (value "0.1uF_25V_0402")
      (footprint "FP-0402-L_1_0_1-W_0_5_0_1-IPC_C")
      (description "General Purpose Ceramic Capacitor, 0402, 100nF, 10%, X7R, 15%, 25V")
      (fields (field (name "VOLTAGE") "25V") (field (name "TOLERANCE") "10%"))
      (libsource (lib "Altium Content Vault") (part "b4654b650e69147ec39a6b967a45e02"))
    )
    (comp (ref "C264")
      (value "10uF_25V_0603")
      (footprint "FP-CL10-IPC_C")
      (description "Cap Ceramic 10uF 25V X5R ±20% Pad SMD 0603 +85°C T/R")
      (fields (field (name "TOLERANCE") "20%"))
      (libsource (lib "Altium Content Vault") (part "b4654b650e69147ec39a6b967a45e02"))
    )
    (comp (ref "C265")
      (value "0.1uF_50V_0402")
      (footprint "FP-C1005-050-0_05-IPC_C")
      (description "Multilayer Ceramic Capacitors 100nF ±10% 50V X7R SMD 0402")
      (fields (field (name "VOLTAGE") "50V") (field (name "TOLERANCE") "10%"))
      (libsource (lib "Altium Content Vault") (part "b4654b650e69147ec39a6b967a45e02"))
    )
    (comp (ref "FB7")
      (value "742792641")
      (footprint "FP-742792641-MFG")
      (description "FERRITE BEAD 300 OHM 0603 1LN")
      (fields (field (name "TOLERANCE") "25%"))
      (libsource (lib "Altium Content Vault") (part "5f30dd21d616792df468990f7003faa"))
    )
    (comp (ref "L1")
      (value "742792780")
      (footprint "SMD-0402")
      (description "SMD EMI Suppression Ferrite Bead WE-CBF, Z = 220 Ohm")
      (libsource (lib "Altium Content Vault") (part "PAS-IND-INDUCTOR-2"))
    )
    (comp (ref "L2")
      (value "742792780")
      (footprint "SMD-0402")
      (description "SMD EMI Suppression Ferrite Bead WE-CBF, Z = 220 Ohm")
      (libsource (lib "Altium Content Vault") (part "PAS-IND-INDUCTOR-2"))
    )
    (comp (ref "L3")
      (value "742792780")
      (footprint "SMD-0402")
      (description "SMD EMI Suppression Ferrite Bead WE-CBF, Z = 220 Ohm")
      (libsource (lib "Altium Content Vault") (part "PAS-IND-INDUCTOR-2"))
    )
    (comp (ref "L4")
      (value "742792780")
      (footprint "SMD-0402")
      (description "SMD EMI Suppression Ferrite Bead WE-CBF, Z = 220 Ohm")
      (libsource (lib "Altium Content Vault") (part "PAS-IND-INDUCTOR-2"))
    )
    (comp (ref "L5")
      (value "742792780")
      (footprint "SMD-0402")
      (description "SMD EMI Suppression Ferrite Bead WE-CBF, Z = 220 Ohm")
      (libsource (lib "Altium Content Vault") (part "PAS-IND-INDUCTOR-2"))
    )
    (comp (ref "L6")
      (value "742792780")
      (footprint "SMD-0402")
      (description "SMD EMI Suppression Ferrite Bead WE-CBF, Z = 220 Ohm")
      (libsource (lib "Altium Content Vault") (part "PAS-IND-INDUCTOR-2"))
    )
    (comp (ref "L7")
      (value "742792780")
      (footprint "SMD-0402")
      (description "SMD EMI Suppression Ferrite Bead WE-CBF, Z = 220 Ohm")
      (libsource (lib "Altium Content Vault") (part "PAS-IND-INDUCTOR-2"))
    )
    (comp (ref "L8")
      (value "742792780")
      (footprint "SMD-0402")
      (description "SMD EMI Suppression Ferrite Bead WE-CBF, Z = 220 Ohm")
      (libsource (lib "Altium Content Vault") (part "PAS-IND-INDUCTOR-2"))
    )
    (comp (ref "L9")
      (value "742792780")
      (footprint "SMD-0402")
      (description "SMD EMI Suppression Ferrite Bead WE-CBF, Z = 220 Ohm")
      (libsource (lib "Altium Content Vault") (part "PAS-IND-INDUCTOR-2"))
    )
    (comp (ref "L10")
      (value "742792780")
      (footprint "SMD-0402")
      (description "SMD EMI Suppression Ferrite Bead WE-CBF, Z = 220 Ohm")
      (libsource (lib "Altium Content Vault") (part "PAS-IND-INDUCTOR-2"))
    )
    (comp (ref "L11")
      (value "742792780")
      (footprint "SMD-0402")
      (description "SMD EMI Suppression Ferrite Bead WE-CBF, Z = 220 Ohm")
      (libsource (lib "Altium Content Vault") (part "PAS-IND-INDUCTOR-2"))
    )
    (comp (ref "L12")
      (value "742792780")
      (footprint "SMD-0402")
      (description "SMD EMI Suppression Ferrite Bead WE-CBF, Z = 220 Ohm")
      (libsource (lib "Altium Content Vault") (part "PAS-IND-INDUCTOR-2"))
    )
    (comp (ref "L13")
      (value "742792780")
      (footprint "SMD-0402")
      (description "SMD EMI Suppression Ferrite Bead WE-CBF, Z = 220 Ohm")
      (libsource (lib "Altium Content Vault") (part "PAS-IND-INDUCTOR-2"))
    )
    (comp (ref "L14")
      (value "742792780")
      (footprint "SMD-0402")
      (description "SMD EMI Suppression Ferrite Bead WE-CBF, Z = 220 Ohm")
      (libsource (lib "Altium Content Vault") (part "PAS-IND-INDUCTOR-2"))
    )
    (comp (ref "L15")
      (value "742792780")
      (footprint "SMD-0402")
      (description "SMD EMI Suppression Ferrite Bead WE-CBF, Z = 220 Ohm")
      (libsource (lib "Altium Content Vault") (part "PAS-IND-INDUCTOR-2"))
    )
    (comp (ref "L16")
      (value "742792780")
      (footprint "SMD-0402")
      (description "SMD EMI Suppression Ferrite Bead WE-CBF, Z = 220 Ohm")
      (libsource (lib "Altium Content Vault") (part "PAS-IND-INDUCTOR-2"))
    )
    (comp (ref "L17")
      (value "742792780")
      (footprint "SMD-0402")
      (description "SMD EMI Suppression Ferrite Bead WE-CBF, Z = 220 Ohm")
      (libsource (lib "Altium Content Vault") (part "PAS-IND-INDUCTOR-2"))
    )
    (comp (ref "L18")
      (value "742792780")
      (footprint "SMD-0402")
      (description "SMD EMI Suppression Ferrite Bead WE-CBF, Z = 220 Ohm")
      (libsource (lib "Altium Content Vault") (part "PAS-IND-INDUCTOR-2"))
    )
    (comp (ref "L24")
      (value "742792780")
      (footprint "SMD-0402")
      (description "SMD EMI Suppression Ferrite Bead WE-CBF, Z = 220 Ohm")
      (libsource (lib "Altium Content Vault") (part "PAS-IND-INDUCTOR-2"))
    )
    (comp (ref "R175")
      (value "0_5%_0402")
      (footprint "RESC1005X40X25LL10T10")
      (fields (field (name "MANUFACTURER") "KOA Speer") (field (name "PART NUMBER") "RK73Z1ETTP"))
      (libsource (lib "Altium Content Vault") (part "RES"))
    )
    (comp (ref "R177")
      (value "0_5%_0402")
      (footprint "RESC1005X40X25LL10T10")
      (fields (field (name "MANUFACTURER") "KOA Speer") (field (name "PART NUMBER") "RK73Z1ETTP"))
      (libsource (lib "Altium Content Vault") (part "RES"))
    )
    (comp (ref "R178")
      (value "100_1%_0402")
      (footprint "RESC1005X40X25ML05T10")
      (fields (field (name "PART NUMBER") "ERJ-U02F1000X") (field (name "MANUFACTURER") "Panasonic"))
      (libsource (lib "Altium Content Vault") (part "RES"))
    )
    (comp (ref "R179")
      (value "49.9_1%_0402")
      (footprint "RESC1005X40X25NL10T10")
      (fields (field (name "PART NUMBER") "RK73H1ETTP49R9F") (field (name "MANUFACTURER") "KOA Speer"))
      (libsource (lib "Altium Content Vault") (part "RES"))
    )
    (comp (ref "R180")
      (value "100_1%_0402")
      (footprint "RESC1005X40X25ML05T10")
      (fields (field (name "PART NUMBER") "ERJ-U02F1000X") (field (name "MANUFACTURER") "Panasonic"))
      (libsource (lib "Altium Content Vault") (part "RES"))
    )
    (comp (ref "R181")
      (value "0_5%_0402")
      (footprint "FP-AC0402-0_37-IPC_B")
      (description "RESISTOR 0402 JUMPER ZERO OHM")
      (fields (field (name "TOLERANCE") "1%"))
      (libsource (lib "Altium Content Vault") (part "1029c3af85768c4190bb7ad29bc67b5"))
    )
    (comp (ref "R182")
      (value "4.7K_1%_0402")
      (footprint "RESC1005X40X25NL10T10")
      (fields (field (name "MANUFACTURER") "Bourns") (field (name "PART NUMBER") "CR0402-FX-4701GLF"))
      (libsource (lib "Altium Content Vault") (part "RES"))
    )
    (comp (ref "R183")
      (value "4.7K_1%_0402")
      (footprint "RESC1005X40X25NL10T10")
      (fields (field (name "MANUFACTURER") "Bourns") (field (name "PART NUMBER") "CR0402-FX-4701GLF"))
      (libsource (lib "Altium Content Vault") (part "RES"))
    )
    (comp (ref "R184")
      (value "4.7K_1%_0402")
      (footprint "RESC1005X40X25NL10T10")
      (fields (field (name "MANUFACTURER") "Bourns") (field (name "PART NUMBER") "CR0402-FX-4701GLF"))
      (libsource (lib "Altium Content Vault") (part "RES"))
    )
    (comp (ref "R264")
      (value "0_1%_0402")
      (footprint "RESC1005X40X25LL05T05")
      (description "Chip Resistor, 0 Ohm, 0.1 W, -55 to 155 degC, 0402 (1005 Metric), RoHS, Tape and Reel")
      (fields (field (name "MANUFACTURER") "Panasonic") (field (name "TOLERANCE") "5%"))
      (libsource (lib "Altium Content Vault") (part "RES-2"))
    )
    (comp (ref "R265")
      (value "0_1%_0402")
      (footprint "RESC1005X40X25LL05T05")
      (description "Chip Resistor, 0 Ohm, 0.1 W, -55 to 155 degC, 0402 (1005 Metric), RoHS, Tape and Reel")
      (fields (field (name "MANUFACTURER") "Panasonic") (field (name "TOLERANCE") "5%"))
      (libsource (lib "Altium Content Vault") (part "RES-2"))
    )
    (comp (ref "Y1")
      (value "ASEMPC-40.000MHZ-XR-T")
      (footprint "FP-ASEMP-CMOS-MFG")
      (description "MEMS Oscillator 40MHz ±25ppm CMOS 2.25V~3.6V 6-SMD 3.2mm x 2.5mm")
      (libsource (lib "Altium Content Vault") (part "9526c112e3a98a1af86e8f4e974a861"))
    )
    (comp (ref "Y2")
      (value "SiTime_SiT5501AC-WU-33E0-10T")
      (footprint "SITIME_SPL-086-CQFN-010-C07050_REV_DRAFT")
      (description "OSC, MEMS, STRATUM 3E, 10.000MHZ, 10PPB STAB, LVCMOS, 3.3V, O/P EN, 7.0X5.0X2.2MM, CQFN-10")
      (fields
        (field (name "MANUFACTURER PART NUMBER") "SiT5501AI-WU033JH-10.000000")
        (field (name "MANUFACTURER") "SiTime")
      )
      (libsource (lib "OCXO_DaughterCard") (part "CMP-OSC-00029-2"))
    )
    (comp (ref "Y6")
      (value "TWETMCJANF-10.000000")
      (footprint "FP-TWETMCJANF-10_000000-MFG")
      (description "XTAL OSC TCXO 10.0000MHZ CMOS")
      (fields
        (field (name "OCTOPART") "https://octopart.com/twetmcjanf-10.000000-taitien-75080612")
        (field (name "MANUFACTURER") "Taitien")
      )
      (libsource (lib "Altium Content Vault") (part "cad4c3239b6ef19b17a0f879cedd8e8"))
    )
  )
  (nets
    (net (code "1") (name "DPLL_CLKIN_5_P") (class "Default")
      (node (ref "R181") (pin "1") (pinfunction "1_1") (pintype "passive"))
    )
    (net (code "2") (name "DPLL_OSCI") (class "Default")
      (node (ref "C249") (pin "2") (pinfunction "2_2") (pintype "passive"))
    )
    (net (code "3") (name "DPLL_VDDA_BG_LC") (class "Default")
      (node (ref "C71") (pin "1") (pinfunction "1_1") (pintype "passive"))
      (node (ref "C72") (pin "1") (pinfunction "1_1") (pintype "passive"))
      (node (ref "C73") (pin "1") (pinfunction "1_1") (pintype "passive"))
      (node (ref "L2") (pin "2") (pinfunction "2_2") (pintype "passive"))
    )
    (net (code "4") (name "DPLL_VDDA_FB") (class "Default")
      (node (ref "C242") (pin "1") (pinfunction "1_1") (pintype "passive"))
      (node (ref "C243") (pin "1") (pinfunction "1_1") (pintype "passive"))
      (node (ref "L14") (pin "2") (pinfunction "2_2") (pintype "passive"))
    )
    (net (code "5") (name "DPLL_VDDA_PDCP_XTAL") (class "Default")
      (node (ref "C170") (pin "1") (pinfunction "1_1") (pintype "passive"))
      (node (ref "C184") (pin "1") (pinfunction "1_1") (pintype "passive"))
      (node (ref "L6") (pin "2") (pinfunction "2_2") (pintype "passive"))
    )
    (net (code "6") (name "DPLL_VDDO_Q0") (class "Default")
      (node (ref "C227") (pin "1") (pinfunction "1_1") (pintype "passive"))
      (node (ref "C228") (pin "1") (pinfunction "1_1") (pintype "passive"))
      (node (ref "L9") (pin "2") (pinfunction "2_2") (pintype "passive"))
    )
    (net (code "7") (name "DPLL_VDDO_Q1") (class "Default")
      (node (ref "C244") (pin "1") (pinfunction "1_1") (pintype "passive"))
      (node (ref "C245") (pin "1") (pinfunction "1_1") (pintype "passive"))
      (node (ref "L13") (pin "2") (pinfunction "2_2") (pintype "passive"))
    )
    (net (code "8") (name "DPLL_VDDO_Q2") (class "Default")
      (node (ref "C253") (pin "1") (pinfunction "1_1") (pintype "passive"))
      (node (ref "C254") (pin "1") (pinfunction "1_1") (pintype "passive"))
      (node (ref "L16") (pin "2") (pinfunction "2_2") (pintype "passive"))
    )
    (net (code "9") (name "DPLL_VDDO_Q3") (class "Default")
      (node (ref "C262") (pin "1") (pinfunction "1_1") (pintype "passive"))
      (node (ref "C263") (pin "1") (pinfunction "1_1") (pintype "passive"))
      (node (ref "L18") (pin "2") (pinfunction "2_2") (pintype "passive"))
    )
    (net (code "10") (name "DPLL_VDDO_Q4") (class "Default")
      (node (ref "C59") (pin "1") (pinfunction "1_1") (pintype "passive"))
      (node (ref "C60") (pin "1") (pinfunction "1_1") (pintype "passive"))
      (node (ref "L1") (pin "2") (pinfunction "2_2") (pintype "passive"))
    )
    (net (code "11") (name "DPLL_VDDO_Q5") (class "Default")
      (node (ref "C84") (pin "1") (pinfunction "1_1") (pintype "passive"))
      (node (ref "C85") (pin "1") (pinfunction "1_1") (pintype "passive"))
      (node (ref "L5") (pin "2") (pinfunction "2_2") (pintype "passive"))
    )
    (net (code "12") (name "DPLL_VDDO_Q6") (class "Default")
      (node (ref "C220") (pin "1") (pinfunction "1_1") (pintype "passive"))
      (node (ref "C221") (pin "1") (pinfunction "1_1") (pintype "passive"))
      (node (ref "L8") (pin "2") (pinfunction "2_2") (pintype "passive"))
    )
    (net (code "13") (name "DPLL_VDDO_Q7") (class "Default")
      (node (ref "C238") (pin "1") (pinfunction "1_1") (pintype "passive"))
      (node (ref "C239") (pin "1") (pinfunction "1_1") (pintype "passive"))
      (node (ref "L12") (pin "2") (pinfunction "2_2") (pintype "passive"))
    )
    (net (code "14") (name "DPLL_VDD_CLKA") (class "Default")
      (node (ref "C247") (pin "1") (pinfunction "1_1") (pintype "passive"))
      (node (ref "C248") (pin "1") (pinfunction "1_1") (pintype "passive"))
      (node (ref "L15") (pin "2") (pinfunction "2_2") (pintype "passive"))
    )
    (net (code "15") (name "DPLL_VDD_CLKB") (class "Default")
      (node (ref "C232") (pin "1") (pinfunction "1_1") (pintype "passive"))
      (node (ref "C233") (pin "1") (pinfunction "1_1") (pintype "passive"))
      (node (ref "L11") (pin "2") (pinfunction "2_2") (pintype "passive"))
    )
    (net (code "16") (name "DPLL_VDD_DCO_Q0123") (class "Default")
      (node (ref "C215") (pin "1") (pinfunction "1_1") (pintype "passive"))
      (node (ref "C216") (pin "1") (pinfunction "1_1") (pintype "passive"))
      (node (ref "L7") (pin "2") (pinfunction "2_2") (pintype "passive"))
    )
    (net (code "17") (name "DPLL_VDD_DCO_Q4567") (class "Default")
      (node (ref "C229") (pin "1") (pinfunction "1_1") (pintype "passive"))
      (node (ref "C230") (pin "1") (pinfunction "1_1") (pintype "passive"))
      (node (ref "L10") (pin "2") (pinfunction "2_2") (pintype "passive"))
    )
    (net (code "18") (name "DPLL_VDD_DIA_A") (class "Default")
      (node (ref "C61") (pin "1") (pinfunction "1_1") (pintype "passive"))
      (node (ref "C62") (pin "1") (pinfunction "1_1") (pintype "passive"))
      (node (ref "L3") (pin "2") (pinfunction "2_2") (pintype "passive"))
    )
    (net (code "19") (name "DPLL_VDD_DIA_B") (class "Default")
      (node (ref "C80") (pin "1") (pinfunction "1_1") (pintype "passive"))
      (node (ref "C81") (pin "1") (pinfunction "1_1") (pintype "passive"))
      (node (ref "L4") (pin "2") (pinfunction "2_2") (pintype "passive"))
    )
    (net (code "20") (name "DPLL_VDD_DIG") (class "Default")
      (node (ref "C63") (pin "1") (pinfunction "1_1") (pintype "passive"))
      (node (ref "C64") (pin "1") (pinfunction "1_1") (pintype "passive"))
      (node (ref "C68") (pin "1") (pinfunction "1_1") (pintype "passive"))
      (node (ref "C69") (pin "1") (pinfunction "1_1") (pintype "passive"))
      (node (ref "R175") (pin "2") (pinfunction "2_2") (pintype "passive"))
    )
    (net (code "21") (name "DPLL_VDD_GPIO") (class "Default")
      (node (ref "C87") (pin "1") (pinfunction "1_1") (pintype "passive"))
      (node (ref "C88") (pin "1") (pinfunction "1_1") (pintype "passive"))
      (node (ref "C89") (pin "1") (pinfunction "1_1") (pintype "passive"))
      (node (ref "C90") (pin "1") (pinfunction "1_1") (pintype "passive"))
      (node (ref "R177") (pin "2") (pinfunction "2_2") (pintype "passive"))
    )
    (net (code "22") (name "DPLL_XO") (class "Default")
      (node (ref "R265") (pin "2") (pinfunction "2_2") (pintype "passive"))
    )
    (net (code "23") (name "GND") (class "Default")
      (node (ref "C170") (pin "2") (pinfunction "2_2") (pintype "passive"))
      (node (ref "C184") (pin "2") (pinfunction "2_2") (pintype "passive"))
      (node (ref "C207") (pin "2") (pinfunction "2_2") (pintype "passive"))
      (node (ref "C208") (pin "2") (pinfunction "2_2") (pintype "passive"))
      (node (ref "C209") (pin "2") (pinfunction "2_2") (pintype "passive"))
      (node (ref "C210") (pin "2") (pinfunction "2_2") (pintype "passive"))
      (node (ref "C211") (pin "2") (pinfunction "2_2") (pintype "passive"))
      (node (ref "C215") (pin "2") (pinfunction "2_2") (pintype "passive"))
      (node (ref "C216") (pin "2") (pinfunction "2_2") (pintype "passive"))
      (node (ref "C217") (pin "2") (pinfunction "2_2") (pintype "passive"))
      (node (ref "C218") (pin "2") (pinfunction "2_2") (pintype "passive"))
      (node (ref "C219") (pin "2") (pinfunction "2_2") (pintype "passive"))
      (node (ref "C220") (pin "2") (pinfunction "2_2") (pintype "passive"))
      (node (ref "C221") (pin "2") (pinfunction "2_2") (pintype "passive"))
      (node (ref "C222") (pin "2") (pinfunction "2_2") (pintype "passive"))
      (node (ref "C223") (pin "2") (pinfunction "2_2") (pintype "passive"))
      (node (ref "C227") (pin "2") (pinfunction "2_2") (pintype "passive"))
      (node (ref "C228") (pin "2") (pinfunction "2_2") (pintype "passive"))
      (node (ref "C229") (pin "2") (pinfunction "2_2") (pintype "passive"))
      (node (ref "C230") (pin "2") (pinfunction "2_2") (pintype "passive"))
      (node (ref "C231") (pin "2") (pinfunction "2_2") (pintype "passive"))
      (node (ref "C232") (pin "2") (pinfunction "2_2") (pintype "passive"))
      (node (ref "C233") (pin "2") (pinfunction "2_2") (pintype "passive"))
      (node (ref "C235") (pin "2") (pinfunction "2_2") (pintype "passive"))
      (node (ref "C236") (pin "2") (pinfunction "2_2") (pintype "passive"))
      (node (ref "C237") (pin "2") (pinfunction "2_2") (pintype "passive"))
      (node (ref "C238") (pin "2") (pinfunction "2_2") (pintype "passive"))
      (node (ref "C239") (pin "2") (pinfunction "2_2") (pintype "passive"))
      (node (ref "C240") (pin "2") (pinfunction "2_2") (pintype "passive"))
      (node (ref "C241") (pin "2") (pinfunction "2_2") (pintype "passive"))
      (node (ref "C242") (pin "2") (pinfunction "2_2") (pintype "passive"))
      (node (ref "C243") (pin "2") (pinfunction "2_2") (pintype "passive"))
      (node (ref "C244") (pin "2") (pinfunction "2_2") (pintype "passive"))
      (node (ref "C245") (pin "2") (pinfunction "2_2") (pintype "passive"))
      (node (ref "C246") (pin "2") (pinfunction "2_2") (pintype "passive"))
      (node (ref "C247") (pin "2") (pinfunction "2_2") (pintype "passive"))
      (node (ref "C248") (pin "2") (pinfunction "2_2") (pintype "passive"))
      (node (ref "C250") (pin "2") (pinfunction "2_2") (pintype "passive"))
      (node (ref "C251") (pin "2") (pinfunction "2_2") (pintype "passive"))
      (node (ref "C252") (pin "2") (pinfunction "2_2") (pintype "passive"))
      (node (ref "C253") (pin "2") (pinfunction "2_2") (pintype "passive"))
      (node (ref "C254") (pin "2") (pinfunction "2_2") (pintype "passive"))
      (node (ref "C255") (pin "2") (pinfunction "2_2") (pintype "passive"))
      (node (ref "C256") (pin "2") (pinfunction "2_2") (pintype "passive"))
      (node (ref "C257") (pin "2") (pinfunction "2_2") (pintype "passive"))
      (node (ref "C258") (pin "2") (pinfunction "2_2") (pintype "passive"))
      (node (ref "C259") (pin "1") (pinfunction "1_1") (pintype "passive"))
      (node (ref "C260") (pin "2") (pinfunction "2_2") (pintype "passive"))
      (node (ref "C261") (pin "2") (pinfunction "2_2") (pintype "passive"))
      (node (ref "C262") (pin "2") (pinfunction "2_2") (pintype "passive"))
      (node (ref "C263") (pin "2") (pinfunction "2_2") (pintype "passive"))
      (node (ref "C264") (pin "2") (pinfunction "2_2") (pintype "passive"))
      (node (ref "C265") (pin "1") (pinfunction "1_1") (pintype "passive"))
      (node (ref "C55") (pin "2") (pinfunction "2_2") (pintype "passive"))
      (node (ref "C56") (pin "2") (pinfunction "2_2") (pintype "passive"))
      (node (ref "C59") (pin "2") (pinfunction "2_2") (pintype "passive"))
      (node (ref "C60") (pin "2") (pinfunction "2_2") (pintype "passive"))
      (node (ref "C61") (pin "2") (pinfunction "2_2") (pintype "passive"))
      (node (ref "C62") (pin "2") (pinfunction "2_2") (pintype "passive"))
      (node (ref "C63") (pin "2") (pinfunction "2_2") (pintype "passive"))
      (node (ref "C64") (pin "2") (pinfunction "2_2") (pintype "passive"))
      (node (ref "C68") (pin "2") (pinfunction "2_2") (pintype "passive"))
      (node (ref "C69") (pin "2") (pinfunction "2_2") (pintype "passive"))
      (node (ref "C71") (pin "2") (pinfunction "2_2") (pintype "passive"))
      (node (ref "C72") (pin "2") (pinfunction "2_2") (pintype "passive"))
      (node (ref "C73") (pin "2") (pinfunction "2_2") (pintype "passive"))
      (node (ref "C74") (pin "2") (pinfunction "2_2") (pintype "passive"))
      (node (ref "C75") (pin "2") (pinfunction "2_2") (pintype "passive"))
      (node (ref "C76") (pin "2") (pinfunction "2_2") (pintype "passive"))
      (node (ref "C77") (pin "2") (pinfunction "2_2") (pintype "passive"))
      (node (ref "C78") (pin "2") (pinfunction "2_2") (pintype "passive"))
      (node (ref "C79") (pin "2") (pinfunction "2_2") (pintype "passive"))
      (node (ref "C80") (pin "2") (pinfunction "2_2") (pintype "passive"))
      (node (ref "C81") (pin "2") (pinfunction "2_2") (pintype "passive"))
      (node (ref "C82") (pin "2") (pinfunction "2_2") (pintype "passive"))
      (node (ref "C83") (pin "2") (pinfunction "2_2") (pintype "passive"))
      (node (ref "C84") (pin "2") (pinfunction "2_2") (pintype "passive"))
      (node (ref "C85") (pin "2") (pinfunction "2_2") (pintype "passive"))
      (node (ref "C86") (pin "2") (pinfunction "2_2") (pintype "passive"))
      (node (ref "C87") (pin "2") (pinfunction "2_2") (pintype "passive"))
      (node (ref "C88") (pin "2") (pinfunction "2_2") (pintype "passive"))
      (node (ref "C89") (pin "2") (pinfunction "2_2") (pintype "passive"))
      (node (ref "C90") (pin "2") (pinfunction "2_2") (pintype "passive"))
      (node (ref "R180") (pin "1") (pinfunction "1_1") (pintype "passive"))
      (node (ref "Y1") (pin "3") (pinfunction "GND_3") (pintype "power_in"))
      (node (ref "Y2") (pin "5") (pinfunction "GND_5") (pintype "power_in"))
      (node (ref "Y6") (pin "1") (pinfunction "GND/NC_1") (pintype "passive"))
      (node (ref "Y6") (pin "2") (pinfunction "GND_2") (pintype "power_in"))
    )
    (net (code "24") (name "Net-(C249-Pad1)") (class "Default")
      (node (ref "C249") (pin "1") (pinfunction "1_1") (pintype "passive"))
      (node (ref "R178") (pin "1") (pinfunction "1_1") (pintype "passive"))
      (node (ref "R179") (pin "2") (pinfunction "2_2") (pintype "passive"))
      (node (ref "R180") (pin "2") (pinfunction "2_2") (pintype "passive"))
    )
    (net (code "25") (name "Net-(R183-Pad1)") (class "Default")
      (node (ref "R183") (pin "1") (pinfunction "1_1") (pintype "passive"))
      (node (ref "Y2") (pin "7") (pinfunction "NC_7") (pintype "passive"))
    )
    (net (code "26") (name "Net-(R184-Pad1)") (class "Default")
      (node (ref "R184") (pin "1") (pinfunction "1_1") (pintype "passive"))
      (node (ref "Y2") (pin "8") (pinfunction "NC_8") (pintype "passive"))
    )
    (net (code "27") (name "Net-(R264-Pad2)") (class "Default")
      (node (ref "R264") (pin "2") (pinfunction "2_2") (pintype "passive"))
      (node (ref "R265") (pin "1") (pinfunction "1_1") (pintype "passive"))
    )
    (net (code "28") (name "Net-(Y1-Output)") (class "Default")
      (node (ref "R179") (pin "1") (pinfunction "1_1") (pintype "passive"))
      (node (ref "Y1") (pin "4") (pinfunction "Output_4") (pintype "output"))
    )
    (net (code "29") (name "Net-(Y1-VDD)") (class "Default")
      (node (ref "C257") (pin "1") (pinfunction "1_1") (pintype "passive"))
      (node (ref "C258") (pin "1") (pinfunction "1_1") (pintype "passive"))
      (node (ref "L17") (pin "2") (pinfunction "2_2") (pintype "passive"))
      (node (ref "Y1") (pin "1") (pinfunction "~{Tri-State}_1") (pintype "input"))
      (node (ref "Y1") (pin "6") (pinfunction "VDD_6") (pintype "power_in"))
    )
    (net (code "30") (name "Net-(Y2-CLK)") (class "Default")
      (node (ref "R181") (pin "2") (pinfunction "2_2") (pintype "passive"))
      (node (ref "Y2") (pin "6") (pinfunction "CLK_6") (pintype "output"))
    )
    (net (code "31") (name "Net-(Y2-OE)") (class "Default")
      (node (ref "R182") (pin "2") (pinfunction "2_2") (pintype "passive"))
      (node (ref "Y2") (pin "1") (pinfunction "OE_1") (pintype "input"))
    )
    (net (code "32") (name "Net-(Y2-VDD)") (class "Default")
      (node (ref "C264") (pin "1") (pinfunction "1_1") (pintype "passive"))
      (node (ref "C265") (pin "2") (pinfunction "2_2") (pintype "passive"))
      (node (ref "FB7") (pin "1") (pinfunction "1_1") (pintype "passive"))
      (node (ref "R182") (pin "1") (pinfunction "1_1") (pintype "passive"))
      (node (ref "Y2") (pin "10") (pinfunction "VDD_10") (pintype "power_in"))
    )
    (net (code "33") (name "Net-(Y6-OUTPUT)") (class "Default")
      (node (ref "R264") (pin "1") (pinfunction "1_1") (pintype "passive"))
      (node (ref "Y6") (pin "3") (pinfunction "OUTPUT_3") (pintype "output"))
    )
    (net (code "34") (name "Net-(Y6-VDD)") (class "Default")
      (node (ref "C210") (pin "1") (pinfunction "1_1") (pintype "passive"))
      (node (ref "C211") (pin "1") (pinfunction "1_1") (pintype "passive"))
      (node (ref "L24") (pin "2") (pinfunction "2_2") (pintype "passive"))
      (node (ref "Y6") (pin "4") (pinfunction "VDD_4") (pintype "power_in"))
    )
    (net (code "35") (name "P1V8") (class "Default")
      (node (ref "C217") (pin "1") (pinfunction "1_1") (pintype "passive"))
      (node (ref "C231") (pin "1") (pinfunction "1_1") (pintype "passive"))
      (node (ref "C246") (pin "1") (pinfunction "1_1") (pintype "passive"))
      (node (ref "C76") (pin "1") (pinfunction "1_1") (pintype "passive"))
      (node (ref "C77") (pin "1") (pinfunction "1_1") (pintype "passive"))
      (node (ref "C78") (pin "1") (pinfunction "1_1") (pintype "passive"))
      (node (ref "C86") (pin "1") (pinfunction "1_1") (pintype "passive"))
      (node (ref "L10") (pin "1") (pinfunction "1_1") (pintype "passive"))
      (node (ref "L14") (pin "1") (pinfunction "1_1") (pintype "passive"))
      (node (ref "L3") (pin "1") (pinfunction "1_1") (pintype "passive"))
      (node (ref "L4") (pin "1") (pinfunction "1_1") (pintype "passive"))
      (node (ref "L7") (pin "1") (pinfunction "1_1") (pintype "passive"))
      (node (ref "R175") (pin "1") (pinfunction "1_1") (pintype "passive"))
    )
    (net (code "36") (name "P3V3") (class "Default")
      (node (ref "C207") (pin "1") (pinfunction "1_1") (pintype "passive"))
      (node (ref "C208") (pin "1") (pinfunction "1_1") (pintype "passive"))
      (node (ref "C209") (pin "1") (pinfunction "1_1") (pintype "passive"))
      (node (ref "C218") (pin "1") (pinfunction "1_1") (pintype "passive"))
      (node (ref "C219") (pin "1") (pinfunction "1_1") (pintype "passive"))
      (node (ref "C222") (pin "1") (pinfunction "1_1") (pintype "passive"))
      (node (ref "C223") (pin "1") (pinfunction "1_1") (pintype "passive"))
      (node (ref "C235") (pin "1") (pinfunction "1_1") (pintype "passive"))
      (node (ref "C236") (pin "1") (pinfunction "1_1") (pintype "passive"))
      (node (ref "C237") (pin "1") (pinfunction "1_1") (pintype "passive"))
      (node (ref "C240") (pin "1") (pinfunction "1_1") (pintype "passive"))
      (node (ref "C241") (pin "1") (pinfunction "1_1") (pintype "passive"))
      (node (ref "C250") (pin "1") (pinfunction "1_1") (pintype "passive"))
      (node (ref "C251") (pin "1") (pinfunction "1_1") (pintype "passive"))
      (node (ref "C252") (pin "1") (pinfunction "1_1") (pintype "passive"))
      (node (ref "C255") (pin "1") (pinfunction "1_1") (pintype "passive"))
      (node (ref "C256") (pin "1") (pinfunction "1_1") (pintype "passive"))
      (node (ref "C259") (pin "2") (pinfunction "2_2") (pintype "passive"))
      (node (ref "C260") (pin "1") (pinfunction "1_1") (pintype "passive"))
      (node (ref "C261") (pin "1") (pinfunction "1_1") (pintype "passive"))
      (node (ref "C55") (pin "1") (pinfunction "1_1") (pintype "passive"))
      (node (ref "C56") (pin "1") (pinfunction "1_1") (pintype "passive"))
      (node (ref "C74") (pin "1") (pinfunction "1_1") (pintype "passive"))
      (node (ref "C75") (pin "1") (pinfunction "1_1") (pintype "passive"))
      (node (ref "C79") (pin "1") (pinfunction "1_1") (pintype "passive"))
      (node (ref "C82") (pin "1") (pinfunction "1_1") (pintype "passive"))
      (node (ref "C83") (pin "1") (pinfunction "1_1") (pintype "passive"))
      (node (ref "FB7") (pin "2") (pinfunction "2_2") (pintype "passive"))
      (node (ref "L1") (pin "1") (pinfunction "1_1") (pintype "passive"))
      (node (ref "L11") (pin "1") (pinfunction "1_1") (pintype "passive"))
      (node (ref "L12") (pin "1") (pinfunction "1_1") (pintype "passive"))
      (node (ref "L13") (pin "1") (pinfunction "1_1") (pintype "passive"))
      (node (ref "L15") (pin "1") (pinfunction "1_1") (pintype "passive"))
      (node (ref "L16") (pin "1") (pinfunction "1_1") (pintype "passive"))
      (node (ref "L17") (pin "1") (pinfunction "1_1") (pintype "passive"))
      (node (ref "L18") (pin "1") (pinfunction "1_1") (pintype "passive"))
      (node (ref "L2") (pin "1") (pinfunction "1_1") (pintype "passive"))
      (node (ref "L24") (pin "1") (pinfunction "1_1") (pintype "passive"))
      (node (ref "L5") (pin "1") (pinfunction "1_1") (pintype "passive"))
      (node (ref "L6") (pin "1") (pinfunction "1_1") (pintype "passive"))
      (node (ref "L8") (pin "1") (pinfunction "1_1") (pintype "passive"))
      (node (ref "L9") (pin "1") (pinfunction "1_1") (pintype "passive"))
      (node (ref "R177") (pin "1") (pinfunction "1_1") (pintype "passive"))
      (node (ref "R178") (pin "2") (pinfunction "2_2") (pintype "passive"))
      (node (ref "R183") (pin "2") (pinfunction "2_2") (pintype "passive"))
      (node (ref "R184") (pin "2") (pinfunction "2_2") (pintype "passive"))
    )
    (net (code "37") (name "SiT5501_PLL_SCL") (class "Default")
      (node (ref "Y2") (pin "3") (pinfunction "NC_3") (pintype "passive"))
    )
    (net (code "38") (name "SiT5501_PLL_SDA") (class "Default")
      (node (ref "Y2") (pin "2") (pinfunction "NC_2") (pintype "passive"))
    )
    (net (code "39") (name "unconnected-(Y2-NC-Pad4)") (class "Default")
      (node (ref "Y2") (pin "4") (pinfunction "NC_4") (pintype "passive"))
    )
    (net (code "40") (name "unconnected-(Y2-NC-Pad9)") (class "Default")
      (node (ref "Y2") (pin "9") (pinfunction "NC_9") (pintype "passive"))
    )
  )
)
